# Simple_4in5_flex.net
KiCad netlist of a schematic drawn in EAGLE
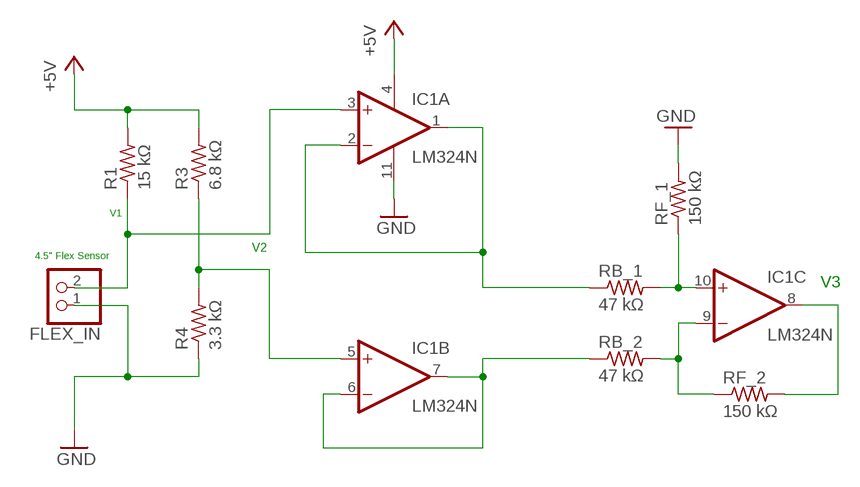
[diagram p0: schematic, sheet 1]

(export (version "E")
  (design (tool "Eeschema 10.0.6"))
  (components
    (comp (ref "FLEX_IN")
      (value "PINHD-1X2")
      (footprint "eagle-import:1X02")
      (libsource (lib "eagle-import") (part "PINHD-1X2"))
    )
    (comp (ref "IC1")
      (value "LM324N")
      (footprint "eagle-import:DIL14")
      (libsource (lib "eagle-import") (part "LM324N"))
    )
    (comp (ref "R1")
      (value "15 kΩ")
      (footprint "eagle-import:0204_5")
      (libsource (lib "eagle-import") (part "R-US_0204/5"))
    )
    (comp (ref "R3")
      (value "6.8 kΩ")
      (footprint "eagle-import:0204_5")
      (libsource (lib "eagle-import") (part "R-US_0204/5"))
    )
    (comp (ref "R4")
      (value "3.3 kΩ")
      (footprint "eagle-import:0204_5")
      (libsource (lib "eagle-import") (part "R-US_0204/5"))
    )
    (comp (ref "RB_1")
      (value "47 kΩ")
      (footprint "eagle-import:0204_5")
      (libsource (lib "eagle-import") (part "resistor_348_R-US_0204/5"))
    )
    (comp (ref "RB_2")
      (value "47 kΩ")
      (footprint "eagle-import:0204_5")
      (libsource (lib "eagle-import") (part "resistor_348_R-US_0204/5"))
    )
    (comp (ref "RF_1")
      (value "150 kΩ")
      (footprint "eagle-import:0204_5")
      (libsource (lib "eagle-import") (part "resistor_348_R-US_0204/5"))
    )
    (comp (ref "RF_2")
      (value "150 kΩ")
      (footprint "eagle-import:0204_5")
      (libsource (lib "eagle-import") (part "resistor_348_R-US_0204/5"))
    )
  )
  (nets
    (net (code "1") (name "+5V") (class "Default")
      (node (ref "IC1") (pin "4") (pinfunction "V+_4") (pintype "power_in"))
      (node (ref "R1") (pin "2") (pinfunction "2_2") (pintype "passive"))
      (node (ref "R3") (pin "2") (pinfunction "2_2") (pintype "passive"))
    )
    (net (code "2") (name "GND") (class "Default")
      (node (ref "FLEX_IN") (pin "1") (pinfunction "1_1") (pintype "passive"))
      (node (ref "IC1") (pin "11") (pinfunction "V-_11") (pintype "power_in"))
      (node (ref "R4") (pin "1") (pinfunction "1_1") (pintype "passive"))
      (node (ref "RF_1") (pin "2") (pinfunction "2_2") (pintype "passive"))
    )
    (net (code "3") (name "Net-(IC1A-+IN)") (class "Default")
      (node (ref "FLEX_IN") (pin "2") (pinfunction "2_2") (pintype "passive"))
      (node (ref "IC1") (pin "3") (pinfunction "+IN_3") (pintype "input"))
      (node (ref "R1") (pin "1") (pinfunction "1_1") (pintype "passive"))
    )
    (net (code "4") (name "Net-(IC1A--IN)") (class "Default")
      (node (ref "IC1") (pin "1") (pinfunction "OUT_1") (pintype "output"))
      (node (ref "IC1") (pin "2") (pinfunction "-IN_2") (pintype "input"))
      (node (ref "RB_1") (pin "1") (pinfunction "1_1") (pintype "passive"))
    )
    (net (code "5") (name "Net-(IC1B-+IN)") (class "Default")
      (node (ref "IC1") (pin "5") (pinfunction "+IN_5") (pintype "input"))
      (node (ref "R3") (pin "1") (pinfunction "1_1") (pintype "passive"))
      (node (ref "R4") (pin "2") (pinfunction "2_2") (pintype "passive"))
    )
    (net (code "6") (name "Net-(IC1B--IN)") (class "Default")
      (node (ref "IC1") (pin "6") (pinfunction "-IN_6") (pintype "input"))
      (node (ref "IC1") (pin "7") (pinfunction "OUT_7") (pintype "output"))
      (node (ref "RB_2") (pin "1") (pinfunction "1_1") (pintype "passive"))
    )
    (net (code "7") (name "Net-(IC1C-+IN)") (class "Default")
      (node (ref "IC1") (pin "10") (pinfunction "+IN_10") (pintype "input"))
      (node (ref "RB_1") (pin "2") (pinfunction "2_2") (pintype "passive"))
      (node (ref "RF_1") (pin "1") (pinfunction "1_1") (pintype "passive"))
    )
    (net (code "8") (name "Net-(IC1C--IN)") (class "Default")
      (node (ref "IC1") (pin "9") (pinfunction "-IN_9") (pintype "input"))
      (node (ref "RB_2") (pin "2") (pinfunction "2_2") (pintype "passive"))
      (node (ref "RF_2") (pin "1") (pinfunction "1_1") (pintype "passive"))
    )
    (net (code "9") (name "Net-(IC1C-OUT)") (class "Default")
      (node (ref "IC1") (pin "8") (pinfunction "OUT_8") (pintype "output"))
      (node (ref "RF_2") (pin "2") (pinfunction "2_2") (pintype "passive"))
    )
  )
)
